# Motor.net
KiCad netlist of a schematic drawn in Altium Designer
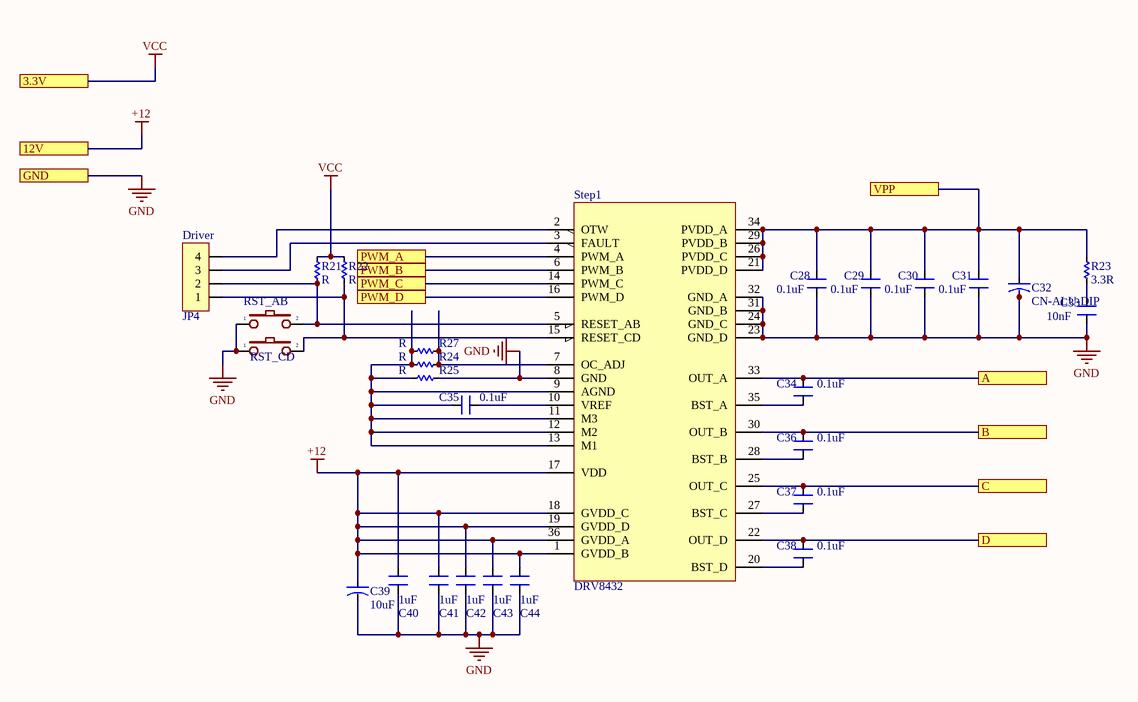
[diagram p0: Motor.SchDoc]

(export (version "E")
  (design (tool "Eeschema 10.0.6"))
  (components
    (comp (ref "C28") (value "0.1uF") (footprint "CN-SMD-0603_big") (libsource (lib "nhan") (part "CN")))
    (comp (ref "C29") (value "0.1uF") (footprint "CN-SMD-0603_big") (libsource (lib "nhan") (part "CN")))
    (comp (ref "C30") (value "0.1uF") (footprint "CN-SMD-0603_big") (libsource (lib "nhan") (part "CN")))
    (comp (ref "C31") (value "0.1uF") (footprint "CN-SMD-0603_big") (libsource (lib "nhan") (part "CN")))
    (comp (ref "C32")
      (value "CN-ALU-DIP")
      (footprint "CA-ALU-5R")
      (description "Capacitor (Semiconductor SIM Model)")
      (fields (field (name "PUBLISHER") "Altium Limited"))
      (libsource (lib "LIBRARY") (part "CN-ALU-DIP"))
    )
    (comp (ref "C33") (value "10nF") (footprint "CN-SMD-0603_big") (libsource (lib "nhan") (part "CN")))
    (comp (ref "C34") (value "0.1uF") (footprint "CN-SMD-0805") (libsource (lib "nhan") (part "CN")))
    (comp (ref "C35") (value "0.1uF") (footprint "CN-SMD-0603_big") (libsource (lib "nhan") (part "CN")))
    (comp (ref "C36") (value "0.1uF") (footprint "CN-SMD-0603_big") (libsource (lib "nhan") (part "CN")))
    (comp (ref "C37") (value "0.1uF") (footprint "CN-SMD-0603_big") (libsource (lib "nhan") (part "CN")))
    (comp (ref "C38") (value "0.1uF") (footprint "CN-SMD-0805") (libsource (lib "nhan") (part "CN")))
    (comp (ref "C39")
      (value "10uF")
      (footprint "CAP-ALU-SMD-6.3x7.7x2.2")
      (description "Polarized Capacitor (Axial)")
      (fields (field (name "PUBLISHER") "Altium Limited"))
      (libsource (lib "LIBRARY") (part "CN-ALU-SMD"))
    )
    (comp (ref "C40") (value "1uF") (footprint "CN-SMD-0603_big") (libsource (lib "nhan") (part "CN")))
    (comp (ref "C41") (value "1uF") (footprint "CN-SMD-0603_big") (libsource (lib "nhan") (part "CN")))
    (comp (ref "C42") (value "1uF") (footprint "CN-SMD-0603_big") (libsource (lib "nhan") (part "CN")))
    (comp (ref "C43") (value "1uF") (footprint "CN-SMD-0603_big") (libsource (lib "nhan") (part "CN")))
    (comp (ref "C44") (value "1uF") (footprint "CN-SMD-0603_big") (libsource (lib "nhan") (part "CN")))
    (comp (ref "Driver")
      (value "JP4")
      (footprint "JP4-C1T")
      (description "WR-PHD 2.54 mm Angled Socket Header")
      (fields
        (field (name "MANUFACTURER") "Würth Elektronik eiSos GmbH")
        (field (name "PARTNO") "613004143121")
        (field (name "CREATED BY") "Karrer Zheng")
      )
      (libsource (lib "LIBRARY") (part "JP4"))
    )
    (comp (ref "R21") (value "R") (footprint "RES-SMD-0603_BIG") (libsource (lib "nhan") (part "R")))
    (comp (ref "R22") (value "R") (footprint "RES-SMD-0603_BIG") (libsource (lib "nhan") (part "R")))
    (comp (ref "R23") (value "3.3R") (footprint "RES-SMD-0603_BIG") (libsource (lib "nhan") (part "R")))
    (comp (ref "R24") (value "R") (footprint "RES-SMD-0603_BIG") (libsource (lib "nhan") (part "R")))
    (comp (ref "R25") (value "R") (footprint "RES-SMD-0603_BIG") (libsource (lib "nhan") (part "R")))
    (comp (ref "R27") (value "R") (footprint "RES-SMD-0603_BIG") (libsource (lib "nhan") (part "R")))
    (comp (ref "RST_AB")
      (value "SW")
      (footprint "SW1-SMD")
      (description "Switch button 2 pin")
      (libsource (lib "BanLinhKien") (part "SW2"))
    )
    (comp (ref "RST_CD")
      (value "SW")
      (footprint "SW1-SMD")
      (description "Switch button 2 pin")
      (libsource (lib "BanLinhKien") (part "SW2"))
    )
    (comp (ref "Step1")
      (value "DRV8432")
      (footprint "DRV8432")
      (description "https://www.digikey.com/product-detail/en/texas-instruments/DRV8432DKDR/296-29573-2-ND/2353367")
      (libsource (lib "nhan") (part "DRV8432"))
    )
  )
  (nets
    (net (code "1") (name "+12") (class "Default")
      (node (ref "C39") (pin "1") (pinfunction "1_1") (pintype "passive"))
      (node (ref "C40") (pin "2") (pinfunction "2_2") (pintype "passive"))
      (node (ref "C41") (pin "2") (pinfunction "2_2") (pintype "passive"))
      (node (ref "C42") (pin "2") (pinfunction "2_2") (pintype "passive"))
      (node (ref "C43") (pin "2") (pinfunction "2_2") (pintype "passive"))
      (node (ref "C44") (pin "2") (pinfunction "2_2") (pintype "passive"))
      (node (ref "Step1") (pin "1") (pinfunction "GVDD_B_1") (pintype "passive"))
      (node (ref "Step1") (pin "17") (pinfunction "VDD_17") (pintype "passive"))
      (node (ref "Step1") (pin "18") (pinfunction "GVDD_C_18") (pintype "passive"))
      (node (ref "Step1") (pin "19") (pinfunction "GVDD_D_19") (pintype "passive"))
      (node (ref "Step1") (pin "36") (pinfunction "GVDD_A_36") (pintype "passive"))
    )
    (net (code "2") (name "/A") (class "Default")
      (node (ref "C34") (pin "2") (pinfunction "2_2") (pintype "passive"))
      (node (ref "Step1") (pin "33") (pinfunction "OUT_A_33") (pintype "passive"))
    )
    (net (code "3") (name "/B") (class "Default")
      (node (ref "C36") (pin "2") (pinfunction "2_2") (pintype "passive"))
      (node (ref "Step1") (pin "30") (pinfunction "OUT_B_30") (pintype "passive"))
    )
    (net (code "4") (name "/C") (class "Default")
      (node (ref "C37") (pin "2") (pinfunction "2_2") (pintype "passive"))
      (node (ref "Step1") (pin "25") (pinfunction "OUT_C_25") (pintype "passive"))
    )
    (net (code "5") (name "/D") (class "Default")
      (node (ref "C38") (pin "2") (pinfunction "2_2") (pintype "passive"))
      (node (ref "Step1") (pin "22") (pinfunction "OUT_D_22") (pintype "passive"))
    )
    (net (code "6") (name "/PWM_A") (class "Default")
      (node (ref "Step1") (pin "4") (pinfunction "PWM_A_4") (pintype "passive"))
    )
    (net (code "7") (name "/PWM_B") (class "Default")
      (node (ref "Step1") (pin "6") (pinfunction "PWM_B_6") (pintype "passive"))
    )
    (net (code "8") (name "/PWM_C") (class "Default")
      (node (ref "Step1") (pin "14") (pinfunction "PWM_C_14") (pintype "passive"))
    )
    (net (code "9") (name "/PWM_D") (class "Default")
      (node (ref "Step1") (pin "16") (pinfunction "PWM_D_16") (pintype "passive"))
    )
    (net (code "10") (name "/VPP") (class "Default")
      (node (ref "C28") (pin "2") (pinfunction "2_2") (pintype "passive"))
      (node (ref "C29") (pin "2") (pinfunction "2_2") (pintype "passive"))
      (node (ref "C30") (pin "2") (pinfunction "2_2") (pintype "passive"))
      (node (ref "C31") (pin "2") (pinfunction "2_2") (pintype "passive"))
      (node (ref "C32") (pin "1") (pinfunction "1_1") (pintype "passive"))
      (node (ref "R23") (pin "1") (pinfunction "1_1") (pintype "passive"))
      (node (ref "Step1") (pin "21") (pinfunction "PVDD_D_21") (pintype "passive"))
      (node (ref "Step1") (pin "26") (pinfunction "PVDD_C_26") (pintype "passive"))
      (node (ref "Step1") (pin "29") (pinfunction "PVDD_B_29") (pintype "passive"))
      (node (ref "Step1") (pin "34") (pinfunction "PVDD_A_34") (pintype "passive"))
    )
    (net (code "11") (name "GND") (class "Default")
      (node (ref "C28") (pin "1") (pinfunction "1_1") (pintype "passive"))
      (node (ref "C29") (pin "1") (pinfunction "1_1") (pintype "passive"))
      (node (ref "C30") (pin "1") (pinfunction "1_1") (pintype "passive"))
      (node (ref "C31") (pin "1") (pinfunction "1_1") (pintype "passive"))
      (node (ref "C32") (pin "2") (pinfunction "2_2") (pintype "passive"))
      (node (ref "C33") (pin "1") (pinfunction "1_1") (pintype "passive"))
      (node (ref "C39") (pin "2") (pinfunction "2_2") (pintype "passive"))
      (node (ref "C40") (pin "1") (pinfunction "1_1") (pintype "passive"))
      (node (ref "C41") (pin "1") (pinfunction "1_1") (pintype "passive"))
      (node (ref "C42") (pin "1") (pinfunction "1_1") (pintype "passive"))
      (node (ref "C43") (pin "1") (pinfunction "1_1") (pintype "passive"))
      (node (ref "C44") (pin "1") (pinfunction "1_1") (pintype "passive"))
      (node (ref "R25") (pin "1") (pinfunction "1_1") (pintype "passive"))
      (node (ref "RST_AB") (pin "1") (pinfunction "1_1") (pintype "passive"))
      (node (ref "RST_CD") (pin "1") (pinfunction "1_1") (pintype "passive"))
      (node (ref "Step1") (pin "23") (pinfunction "GND_D_23") (pintype "passive"))
      (node (ref "Step1") (pin "24") (pinfunction "GND_C_24") (pintype "passive"))
      (node (ref "Step1") (pin "31") (pinfunction "GND_B_31") (pintype "passive"))
      (node (ref "Step1") (pin "32") (pinfunction "GND_A_32") (pintype "passive"))
      (node (ref "Step1") (pin "8") (pinfunction "GND_8") (pintype "passive"))
    )
    (net (code "12") (name "Net-(C33-Pad2)") (class "Default")
      (node (ref "C33") (pin "2") (pinfunction "2_2") (pintype "passive"))
      (node (ref "R23") (pin "2") (pinfunction "2_2") (pintype "passive"))
    )
    (net (code "13") (name "Net-(Step1-AGND)") (class "Default")
      (node (ref "C35") (pin "2") (pinfunction "2_2") (pintype "passive"))
      (node (ref "R24") (pin "2") (pinfunction "2_2") (pintype "passive"))
      (node (ref "R25") (pin "2") (pinfunction "2_2") (pintype "passive"))
      (node (ref "R27") (pin "2") (pinfunction "2_2") (pintype "passive"))
      (node (ref "Step1") (pin "11") (pinfunction "M3_11") (pintype "passive"))
      (node (ref "Step1") (pin "12") (pinfunction "M2_12") (pintype "passive"))
      (node (ref "Step1") (pin "13") (pinfunction "M1_13") (pintype "passive"))
      (node (ref "Step1") (pin "9") (pinfunction "AGND_9") (pintype "passive"))
    )
    (net (code "14") (name "Net-(Step1-BST_A)") (class "Default")
      (node (ref "C34") (pin "1") (pinfunction "1_1") (pintype "passive"))
      (node (ref "Step1") (pin "35") (pinfunction "BST_A_35") (pintype "passive"))
    )
    (net (code "15") (name "Net-(Step1-BST_B)") (class "Default")
      (node (ref "C36") (pin "1") (pinfunction "1_1") (pintype "passive"))
      (node (ref "Step1") (pin "28") (pinfunction "BST_B_28") (pintype "passive"))
    )
    (net (code "16") (name "Net-(Step1-BST_C)") (class "Default")
      (node (ref "C37") (pin "1") (pinfunction "1_1") (pintype "passive"))
      (node (ref "Step1") (pin "27") (pinfunction "BST_C_27") (pintype "passive"))
    )
    (net (code "17") (name "Net-(Step1-BST_D)") (class "Default")
      (node (ref "C38") (pin "1") (pinfunction "1_1") (pintype "passive"))
      (node (ref "Step1") (pin "20") (pinfunction "BST_D_20") (pintype "passive"))
    )
    (net (code "18") (name "Net-(Step1-FAULT)") (class "Default")
      (node (ref "Driver") (pin "3") (pinfunction "3_3") (pintype "passive"))
      (node (ref "Step1") (pin "3") (pinfunction "FAULT_3") (pintype "power_in"))
    )
    (net (code "19") (name "Net-(Step1-OC_ADJ)") (class "Default")
      (node (ref "R24") (pin "1") (pinfunction "1_1") (pintype "passive"))
      (node (ref "R27") (pin "1") (pinfunction "1_1") (pintype "passive"))
      (node (ref "Step1") (pin "7") (pinfunction "OC_ADJ_7") (pintype "passive"))
    )
    (net (code "20") (name "Net-(Step1-OTW)") (class "Default")
      (node (ref "Driver") (pin "4") (pinfunction "4_4") (pintype "passive"))
      (node (ref "Step1") (pin "2") (pinfunction "OTW_2") (pintype "passive"))
    )
    (net (code "21") (name "Net-(Step1-RESET_AB)") (class "Default")
      (node (ref "Driver") (pin "2") (pinfunction "2_2") (pintype "passive"))
      (node (ref "R21") (pin "2") (pinfunction "2_2") (pintype "passive"))
      (node (ref "RST_AB") (pin "2") (pinfunction "2_2") (pintype "passive"))
      (node (ref "Step1") (pin "5") (pinfunction "RESET_AB_5") (pintype "passive"))
    )
    (net (code "22") (name "Net-(Step1-RESET_CD)") (class "Default")
      (node (ref "Driver") (pin "1") (pinfunction "1_1") (pintype "passive"))
      (node (ref "R22") (pin "2") (pinfunction "2_2") (pintype "passive"))
      (node (ref "RST_CD") (pin "2") (pinfunction "2_2") (pintype "passive"))
      (node (ref "Step1") (pin "15") (pinfunction "RESET_CD_15") (pintype "passive"))
    )
    (net (code "23") (name "Net-(Step1-VREF)") (class "Default")
      (node (ref "C35") (pin "1") (pinfunction "1_1") (pintype "passive"))
      (node (ref "Step1") (pin "10") (pinfunction "VREF_10") (pintype "passive"))
    )
    (net (code "24") (name "VCC") (class "Default")
      (node (ref "R21") (pin "1") (pinfunction "1_1") (pintype "passive"))
      (node (ref "R22") (pin "1") (pinfunction "1_1") (pintype "passive"))
    )
  )
)
